# CapstoneProject16_latest.net
KiCad netlist of a schematic drawn in EAGLE
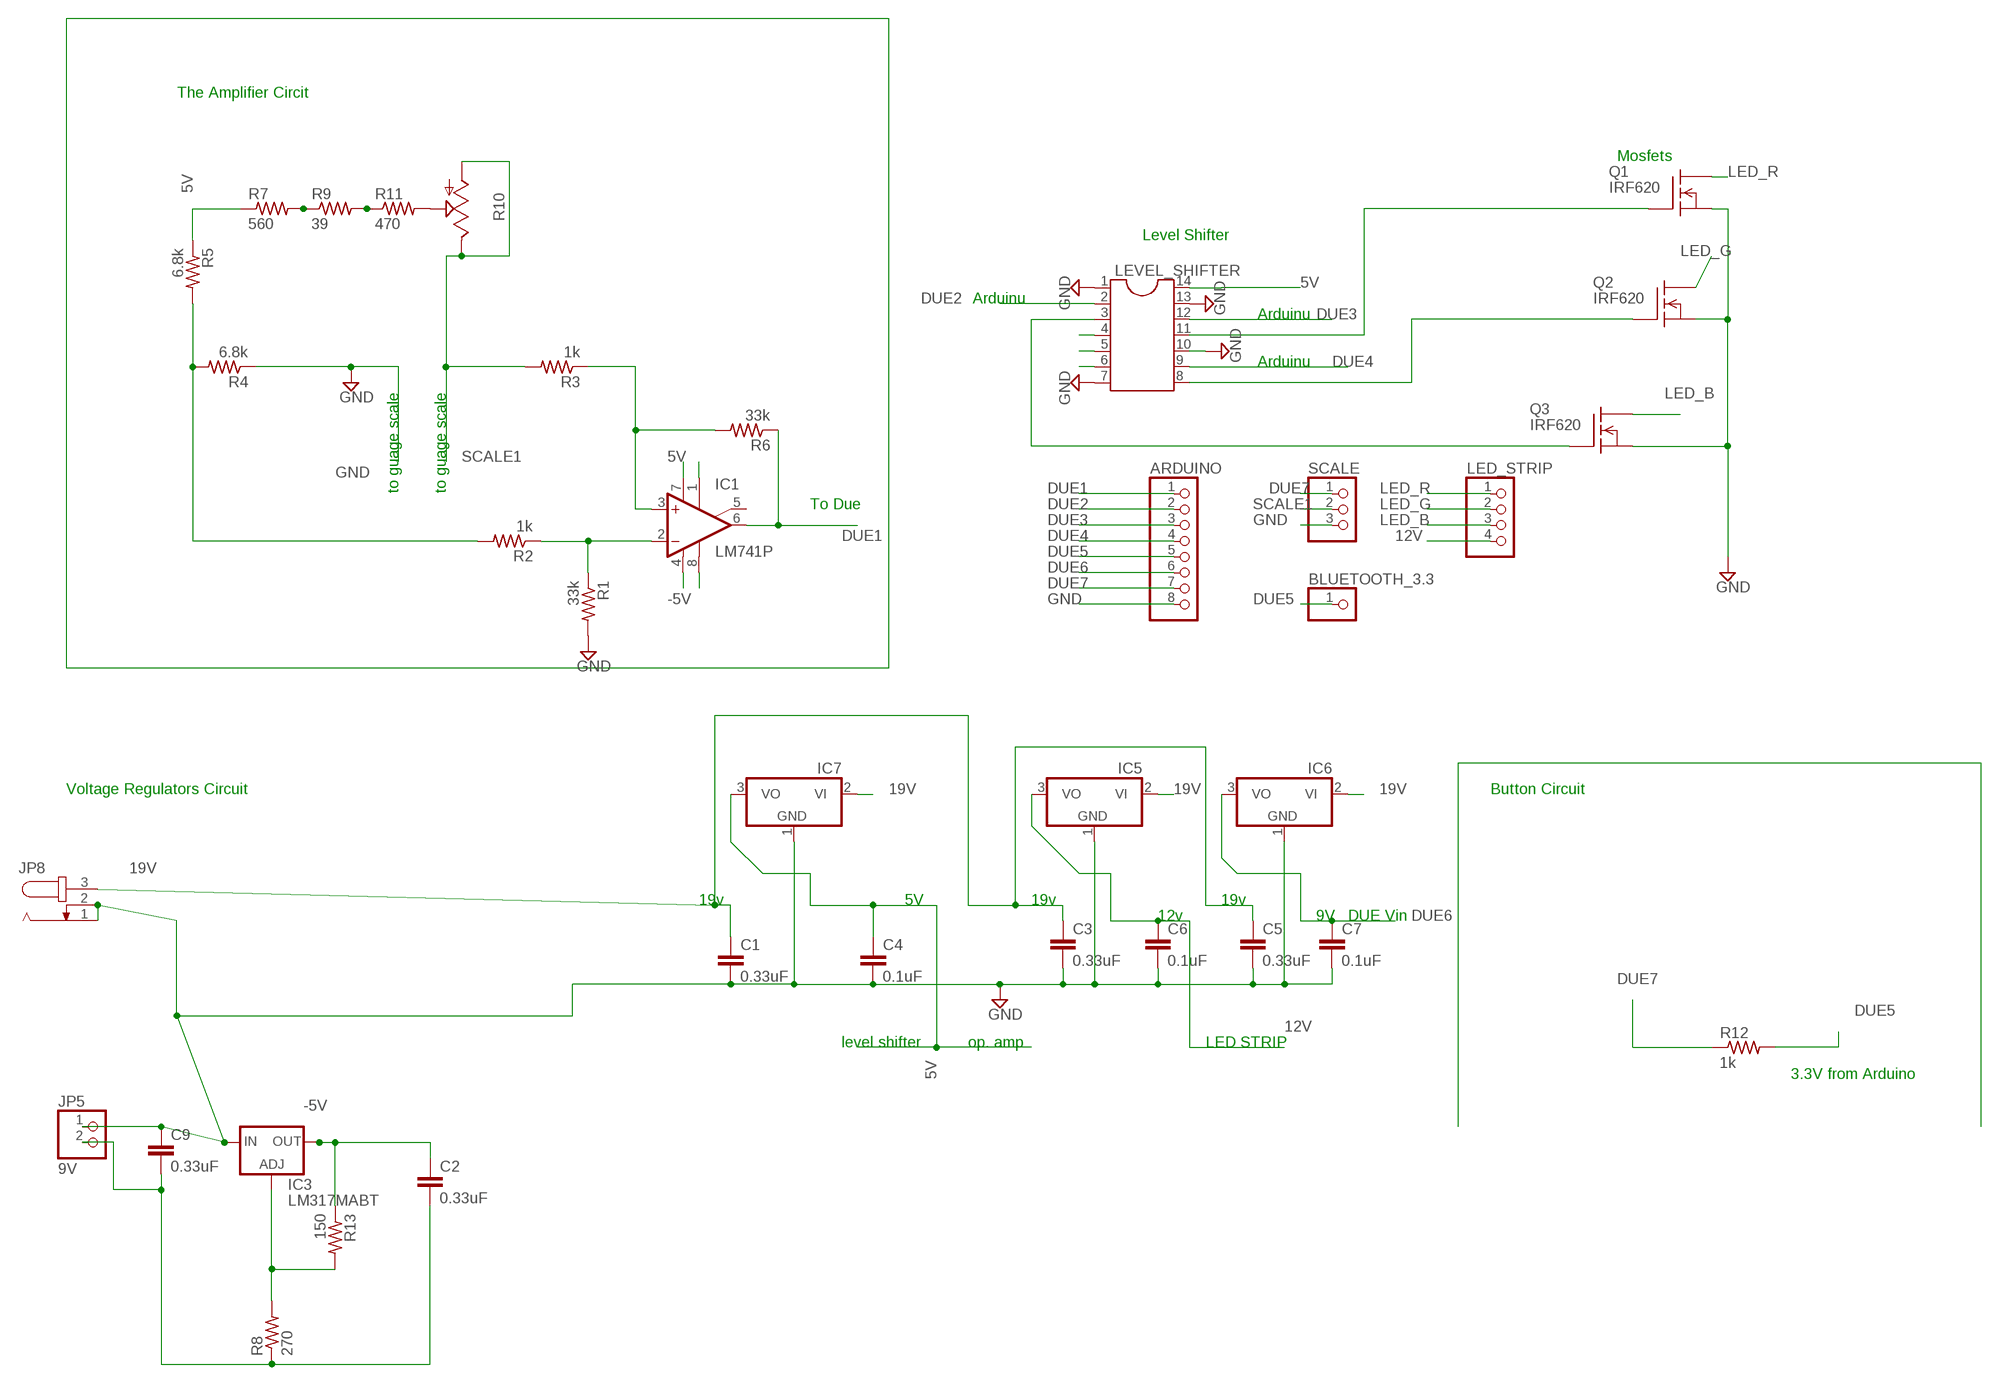
[diagram p0: schematic, sheet 1]

(export (version "E")
  (design (tool "Eeschema 10.0.6"))
  (components
    (comp (ref "ARDUINO")
      (value "PINHD-1X8")
      (footprint "eagle-import:1X08")
      (libsource (lib "eagle-import") (part "PINHD-1X8"))
    )
    (comp (ref "BLUETOOTH_3.3")
      (value "PINHD-1X1")
      (footprint "eagle-import:1X01")
      (libsource (lib "eagle-import") (part "PINHD-1X1"))
    )
    (comp (ref "C1")
      (value "0.33uF")
      (footprint "eagle-import:C2.5-3")
      (libsource (lib "eagle-import") (part "C2,5-3"))
    )
    (comp (ref "C2")
      (value "0.33uF")
      (footprint "eagle-import:C2.5-3")
      (libsource (lib "eagle-import") (part "C2,5-3"))
    )
    (comp (ref "C3")
      (value "0.33uF")
      (footprint "eagle-import:C2.5-3")
      (libsource (lib "eagle-import") (part "C2,5-3"))
    )
    (comp (ref "C4")
      (value "0.1uF")
      (footprint "eagle-import:C2.5-3")
      (libsource (lib "eagle-import") (part "C2,5-3"))
    )
    (comp (ref "C5")
      (value "0.33uF")
      (footprint "eagle-import:C2.5-3")
      (libsource (lib "eagle-import") (part "C2,5-3"))
    )
    (comp (ref "C6")
      (value "0.1uF")
      (footprint "eagle-import:C2.5-3")
      (libsource (lib "eagle-import") (part "C2,5-3"))
    )
    (comp (ref "C7")
      (value "0.1uF")
      (footprint "eagle-import:C2.5-3")
      (libsource (lib "eagle-import") (part "C2,5-3"))
    )
    (comp (ref "C9")
      (value "0.33uF")
      (footprint "eagle-import:C2.5-3")
      (libsource (lib "eagle-import") (part "C2,5-3"))
    )
    (comp (ref "IC1")
      (value "LM741P")
      (footprint "eagle-import:DIL08")
      (libsource (lib "eagle-import") (part "741PLM"))
    )
    (comp (ref "IC3")
      (value "LM317MABT")
      (footprint "eagle-import:TO220L1")
      (libsource (lib "eagle-import") (part "LM317?MABT"))
    )
    (comp (ref "IC5")
      (value "7905T")
      (footprint "eagle-import:TO220H")
      (libsource (lib "eagle-import") (part "79T05"))
    )
    (comp (ref "IC6")
      (value "7905T")
      (footprint "eagle-import:TO220H")
      (libsource (lib "eagle-import") (part "79T05"))
    )
    (comp (ref "IC7")
      (value "79L05Z")
      (footprint "eagle-import:TO92")
      (libsource (lib "eagle-import") (part "79ZL05"))
    )
    (comp (ref "JP5")
      (value "9V")
      (footprint "eagle-import:1X02")
      (libsource (lib "eagle-import") (part "PINHD-1X2"))
    )
    (comp (ref "JP8")
      (value "JACK-PLUG1")
      (footprint "eagle-import:SPC4078")
      (libsource (lib "eagle-import") (part "JACK-PLUG1"))
    )
    (comp (ref "LED_STRIP")
      (value "PINHD-1X4")
      (footprint "eagle-import:1X04")
      (libsource (lib "eagle-import") (part "PINHD-1X4"))
    )
    (comp (ref "LEVEL_SHIFTER")
      (value "DIL14")
      (footprint "eagle-import:DIL14")
      (libsource (lib "eagle-import") (part "DIL14"))
    )
    (comp (ref "Q1")
      (value "IRF620")
      (footprint "eagle-import:TO220")
      (libsource (lib "eagle-import") (part "IRF620"))
    )
    (comp (ref "Q2")
      (value "IRF620")
      (footprint "eagle-import:TO220")
      (libsource (lib "eagle-import") (part "IRF620"))
    )
    (comp (ref "Q3")
      (value "IRF620")
      (footprint "eagle-import:TO220")
      (libsource (lib "eagle-import") (part "IRF620"))
    )
    (comp (ref "R1")
      (value "33k")
      (footprint "eagle-import:0204_7")
      (libsource (lib "eagle-import") (part "R-US_0204/7"))
    )
    (comp (ref "R2")
      (value "1k")
      (footprint "eagle-import:0204_7")
      (libsource (lib "eagle-import") (part "R-US_0204/7"))
    )
    (comp (ref "R3")
      (value "1k")
      (footprint "eagle-import:0204_7")
      (libsource (lib "eagle-import") (part "R-US_0204/7"))
    )
    (comp (ref "R4")
      (value "6.8k")
      (footprint "eagle-import:0204_7")
      (libsource (lib "eagle-import") (part "R-US_0204/7"))
    )
    (comp (ref "R5")
      (value "6.8k")
      (footprint "eagle-import:0204_7")
      (libsource (lib "eagle-import") (part "R-US_0204/7"))
    )
    (comp (ref "R6")
      (value "33k")
      (footprint "eagle-import:0204_7")
      (libsource (lib "eagle-import") (part "R-US_0204/7"))
    )
    (comp (ref "R7")
      (value "560")
      (footprint "eagle-import:0204_7")
      (libsource (lib "eagle-import") (part "R-US_0204/7"))
    )
    (comp (ref "R8")
      (value "270")
      (footprint "eagle-import:0204_7")
      (libsource (lib "eagle-import") (part "R-US_0204/7"))
    )
    (comp (ref "R9")
      (value "39")
      (footprint "eagle-import:0204_7")
      (libsource (lib "eagle-import") (part "R-US_0204/7"))
    )
    (comp (ref "R10")
      (value "TRIM_US-S63P")
      (footprint "eagle-import:S63P")
      (libsource (lib "eagle-import") (part "TRIM_US-S63P"))
    )
    (comp (ref "R11")
      (value "470")
      (footprint "eagle-import:0204_7")
      (libsource (lib "eagle-import") (part "R-US_0204/7"))
    )
    (comp (ref "R12")
      (value "1k")
      (footprint "eagle-import:0204_7")
      (libsource (lib "eagle-import") (part "R-US_0204/7"))
    )
    (comp (ref "R13")
      (value "150")
      (footprint "eagle-import:0204_7")
      (libsource (lib "eagle-import") (part "R-US_0204/7"))
    )
    (comp (ref "SCALE")
      (value "PINHD-1X3")
      (footprint "eagle-import:1X03")
      (libsource (lib "eagle-import") (part "PINHD-1X3"))
    )
  )
  (nets
    (net (code "1") (name "/-5V") (class "Default")
      (node (ref "C2") (pin "1") (pinfunction "1_1") (pintype "passive"))
      (node (ref "IC1") (pin "4") (pinfunction "V-_4") (pintype "power_in"))
      (node (ref "IC3") (pin "2") (pinfunction "OUT_2") (pintype "passive"))
      (node (ref "R13") (pin "1") (pinfunction "1_1") (pintype "passive"))
    )
    (net (code "2") (name "/5V") (class "Default")
      (node (ref "C4") (pin "1") (pinfunction "1_1") (pintype "passive"))
      (node (ref "IC1") (pin "7") (pinfunction "V+_7") (pintype "power_in"))
      (node (ref "IC7") (pin "3") (pinfunction "VO_3") (pintype "passive"))
      (node (ref "LEVEL_SHIFTER") (pin "14") (pinfunction "14_14") (pintype "passive"))
      (node (ref "R5") (pin "1") (pinfunction "1_1") (pintype "passive"))
      (node (ref "R7") (pin "1") (pinfunction "1_1") (pintype "passive"))
    )
    (net (code "3") (name "/12V") (class "Default")
      (node (ref "C6") (pin "1") (pinfunction "1_1") (pintype "passive"))
      (node (ref "IC5") (pin "3") (pinfunction "VO_3") (pintype "passive"))
      (node (ref "LED_STRIP") (pin "4") (pinfunction "4_4") (pintype "passive"))
    )
    (net (code "4") (name "/19V") (class "Default")
      (node (ref "C1") (pin "1") (pinfunction "1_1") (pintype "passive"))
      (node (ref "C3") (pin "1") (pinfunction "1_1") (pintype "passive"))
      (node (ref "C5") (pin "1") (pinfunction "1_1") (pintype "passive"))
      (node (ref "IC5") (pin "2") (pinfunction "VI_2") (pintype "input"))
      (node (ref "IC6") (pin "2") (pinfunction "VI_2") (pintype "input"))
      (node (ref "IC7") (pin "2") (pinfunction "VI_2") (pintype "input"))
      (node (ref "JP8") (pin "3") (pinfunction "3_3") (pintype "passive"))
    )
    (net (code "5") (name "/DUE1") (class "Default")
      (node (ref "ARDUINO") (pin "1") (pinfunction "1_1") (pintype "passive"))
      (node (ref "IC1") (pin "6") (pinfunction "OUT_6") (pintype "output"))
      (node (ref "R6") (pin "1") (pinfunction "1_1") (pintype "passive"))
    )
    (net (code "6") (name "/DUE2") (class "Default")
      (node (ref "ARDUINO") (pin "2") (pinfunction "2_2") (pintype "passive"))
      (node (ref "LEVEL_SHIFTER") (pin "2") (pinfunction "2_2") (pintype "passive"))
    )
    (net (code "7") (name "/DUE3") (class "Default")
      (node (ref "ARDUINO") (pin "3") (pinfunction "3_3") (pintype "passive"))
      (node (ref "LEVEL_SHIFTER") (pin "12") (pinfunction "12_12") (pintype "passive"))
    )
    (net (code "8") (name "/DUE4") (class "Default")
      (node (ref "ARDUINO") (pin "4") (pinfunction "4_4") (pintype "passive"))
      (node (ref "LEVEL_SHIFTER") (pin "9") (pinfunction "9_9") (pintype "passive"))
    )
    (net (code "9") (name "/DUE5") (class "Default")
      (node (ref "ARDUINO") (pin "5") (pinfunction "5_5") (pintype "passive"))
      (node (ref "BLUETOOTH_3.3") (pin "1") (pinfunction "1_1") (pintype "passive"))
      (node (ref "R12") (pin "2") (pinfunction "2_2") (pintype "passive"))
    )
    (net (code "10") (name "/DUE6") (class "Default")
      (node (ref "ARDUINO") (pin "6") (pinfunction "6_6") (pintype "passive"))
      (node (ref "C7") (pin "1") (pinfunction "1_1") (pintype "passive"))
      (node (ref "IC6") (pin "3") (pinfunction "VO_3") (pintype "passive"))
    )
    (net (code "11") (name "/DUE7") (class "Default")
      (node (ref "ARDUINO") (pin "7") (pinfunction "7_7") (pintype "passive"))
      (node (ref "R12") (pin "1") (pinfunction "1_1") (pintype "passive"))
      (node (ref "SCALE") (pin "1") (pinfunction "1_1") (pintype "passive"))
    )
    (net (code "12") (name "/LED_B") (class "Default")
      (node (ref "LED_STRIP") (pin "3") (pinfunction "3_3") (pintype "passive"))
      (node (ref "Q3") (pin "2") (pinfunction "D_2") (pintype "passive"))
    )
    (net (code "13") (name "/LED_G") (class "Default")
      (node (ref "LED_STRIP") (pin "2") (pinfunction "2_2") (pintype "passive"))
      (node (ref "Q2") (pin "2") (pinfunction "D_2") (pintype "passive"))
    )
    (net (code "14") (name "/LED_R") (class "Default")
      (node (ref "LED_STRIP") (pin "1") (pinfunction "1_1") (pintype "passive"))
      (node (ref "Q1") (pin "2") (pinfunction "D_2") (pintype "passive"))
    )
    (net (code "15") (name "/SCALE1") (class "Default")
      (node (ref "R10") (pin "A") (pinfunction "A_A") (pintype "passive"))
      (node (ref "R10") (pin "E") (pinfunction "E_E") (pintype "passive"))
      (node (ref "R3") (pin "2") (pinfunction "2_2") (pintype "passive"))
      (node (ref "SCALE") (pin "2") (pinfunction "2_2") (pintype "passive"))
    )
    (net (code "16") (name "GND") (class "Default")
      (node (ref "ARDUINO") (pin "8") (pinfunction "8_8") (pintype "passive"))
      (node (ref "C1") (pin "2") (pinfunction "2_2") (pintype "passive"))
      (node (ref "C3") (pin "2") (pinfunction "2_2") (pintype "passive"))
      (node (ref "C4") (pin "2") (pinfunction "2_2") (pintype "passive"))
      (node (ref "C5") (pin "2") (pinfunction "2_2") (pintype "passive"))
      (node (ref "C6") (pin "2") (pinfunction "2_2") (pintype "passive"))
      (node (ref "C7") (pin "2") (pinfunction "2_2") (pintype "passive"))
      (node (ref "C9") (pin "1") (pinfunction "1_1") (pintype "passive"))
      (node (ref "IC3") (pin "3") (pinfunction "IN_3") (pintype "input"))
      (node (ref "IC5") (pin "1") (pinfunction "GND_1") (pintype "passive"))
      (node (ref "IC6") (pin "1") (pinfunction "GND_1") (pintype "passive"))
      (node (ref "IC7") (pin "1") (pinfunction "GND_1") (pintype "passive"))
      (node (ref "JP5") (pin "1") (pinfunction "1_1") (pintype "passive"))
      (node (ref "JP8") (pin "1") (pinfunction "1_1") (pintype "passive"))
      (node (ref "JP8") (pin "2") (pinfunction "2_2") (pintype "passive"))
      (node (ref "LEVEL_SHIFTER") (pin "1") (pinfunction "1_1") (pintype "passive"))
      (node (ref "LEVEL_SHIFTER") (pin "10") (pinfunction "10_10") (pintype "passive"))
      (node (ref "LEVEL_SHIFTER") (pin "13") (pinfunction "13_13") (pintype "passive"))
      (node (ref "LEVEL_SHIFTER") (pin "7") (pinfunction "7_7") (pintype "passive"))
      (node (ref "Q1") (pin "3") (pinfunction "S_3") (pintype "passive"))
      (node (ref "Q2") (pin "3") (pinfunction "S_3") (pintype "passive"))
      (node (ref "Q3") (pin "3") (pinfunction "S_3") (pintype "passive"))
      (node (ref "R1") (pin "2") (pinfunction "2_2") (pintype "passive"))
      (node (ref "R4") (pin "1") (pinfunction "1_1") (pintype "passive"))
      (node (ref "SCALE") (pin "3") (pinfunction "3_3") (pintype "passive"))
    )
    (net (code "17") (name "Net-(C2-Pad2)") (class "Default")
      (node (ref "C2") (pin "2") (pinfunction "2_2") (pintype "passive"))
      (node (ref "C9") (pin "2") (pinfunction "2_2") (pintype "passive"))
      (node (ref "JP5") (pin "2") (pinfunction "2_2") (pintype "passive"))
      (node (ref "R8") (pin "1") (pinfunction "1_1") (pintype "passive"))
    )
    (net (code "18") (name "Net-(IC1-+IN)") (class "Default")
      (node (ref "IC1") (pin "3") (pinfunction "+IN_3") (pintype "input"))
      (node (ref "R3") (pin "1") (pinfunction "1_1") (pintype "passive"))
      (node (ref "R6") (pin "2") (pinfunction "2_2") (pintype "passive"))
    )
    (net (code "19") (name "Net-(IC1--IN)") (class "Default")
      (node (ref "IC1") (pin "2") (pinfunction "-IN_2") (pintype "input"))
      (node (ref "R1") (pin "1") (pinfunction "1_1") (pintype "passive"))
      (node (ref "R2") (pin "1") (pinfunction "1_1") (pintype "passive"))
    )
    (net (code "20") (name "Net-(IC3-ADJ)") (class "Default")
      (node (ref "IC3") (pin "1") (pinfunction "ADJ_1") (pintype "input"))
      (node (ref "R13") (pin "2") (pinfunction "2_2") (pintype "passive"))
      (node (ref "R8") (pin "2") (pinfunction "2_2") (pintype "passive"))
    )
    (net (code "21") (name "Net-(Q1-G)") (class "Default")
      (node (ref "LEVEL_SHIFTER") (pin "11") (pinfunction "11_11") (pintype "passive"))
      (node (ref "Q1") (pin "1") (pinfunction "G_1") (pintype "passive"))
    )
    (net (code "22") (name "Net-(Q2-G)") (class "Default")
      (node (ref "LEVEL_SHIFTER") (pin "8") (pinfunction "8_8") (pintype "passive"))
      (node (ref "Q2") (pin "1") (pinfunction "G_1") (pintype "passive"))
    )
    (net (code "23") (name "Net-(Q3-G)") (class "Default")
      (node (ref "LEVEL_SHIFTER") (pin "3") (pinfunction "3_3") (pintype "passive"))
      (node (ref "Q3") (pin "1") (pinfunction "G_1") (pintype "passive"))
    )
    (net (code "24") (name "Net-(R2-Pad2)") (class "Default")
      (node (ref "R2") (pin "2") (pinfunction "2_2") (pintype "passive"))
      (node (ref "R4") (pin "2") (pinfunction "2_2") (pintype "passive"))
      (node (ref "R5") (pin "2") (pinfunction "2_2") (pintype "passive"))
    )
    (net (code "25") (name "Net-(R7-Pad2)") (class "Default")
      (node (ref "R7") (pin "2") (pinfunction "2_2") (pintype "passive"))
      (node (ref "R9") (pin "1") (pinfunction "1_1") (pintype "passive"))
    )
    (net (code "26") (name "Net-(R10-PadS)") (class "Default")
      (node (ref "R10") (pin "S") (pinfunction "S_S") (pintype "passive"))
      (node (ref "R11") (pin "2") (pinfunction "2_2") (pintype "passive"))
    )
    (net (code "27") (name "Net-(R11-Pad1)") (class "Default")
      (node (ref "R11") (pin "1") (pinfunction "1_1") (pintype "passive"))
      (node (ref "R9") (pin "2") (pinfunction "2_2") (pintype "passive"))
    )
    (net (code "28") (name "unconnected-(IC1-ON1-Pad1)") (class "Default")
      (node (ref "IC1") (pin "1") (pinfunction "ON1_1") (pintype "passive"))
    )
    (net (code "29") (name "unconnected-(IC1-ON2-Pad5)") (class "Default")
      (node (ref "IC1") (pin "5") (pinfunction "ON2_5") (pintype "passive"))
    )
    (net (code "30") (name "unconnected-(IC1-OPT-Pad8)") (class "Default")
      (node (ref "IC1") (pin "8") (pinfunction "OPT_8") (pintype "passive"))
    )
    (net (code "31") (name "unconnected-(LEVEL_SHIFTER-Pad4)") (class "Default")
      (node (ref "LEVEL_SHIFTER") (pin "4") (pinfunction "4_4") (pintype "passive"))
    )
    (net (code "32") (name "unconnected-(LEVEL_SHIFTER-Pad5)") (class "Default")
      (node (ref "LEVEL_SHIFTER") (pin "5") (pinfunction "5_5") (pintype "passive"))
    )
    (net (code "33") (name "unconnected-(LEVEL_SHIFTER-Pad6)") (class "Default")
      (node (ref "LEVEL_SHIFTER") (pin "6") (pinfunction "6_6") (pintype "passive"))
    )
  )
)
